# Schematic.net
KiCad netlist of a schematic drawn in Altium Designer
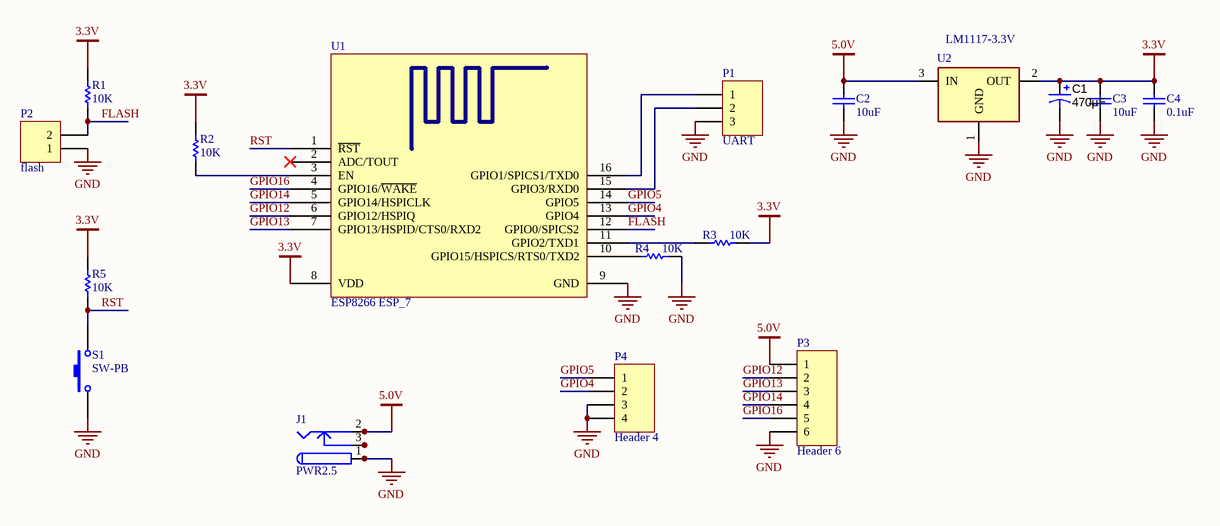
[diagram p0: Schematic.SchDoc]

(export (version "E")
  (design (tool "Eeschema 10.0.6"))
  (components
    (comp (ref "C1")
      (value "T495E477K010ATE040")
      (footprint "7260-38")
      (description "CAP, TANT, 470uF, 10V, +/-10%, 0.04 ohm, 7260-38 SMD")
      (fields
        (field (name "MANUFACTURER") "Kemet")
        (field (name "VALUEDISPLAYED") "470µF")
        (field (name "PUBLISHER") "Texas Instruments")
      )
      (libsource (lib "Schlib1") (part "T495E477K010ATE040"))
    )
    (comp (ref "C2")
      (value "10uF")
      (footprint "C1206")
      (description "Capacitor (Semiconductor SIM Model)")
      (fields (field (name "Comment") "Cap Semi") (field (name "PUBLISHER") "Altium Limited"))
      (libsource (lib "Miscellaneous Devices") (part "Cap Semi"))
    )
    (comp (ref "C3")
      (value "10uF")
      (footprint "C1206")
      (description "Capacitor (Semiconductor SIM Model)")
      (fields (field (name "Comment") "Cap Semi") (field (name "PUBLISHER") "Altium Limited"))
      (libsource (lib "Miscellaneous Devices") (part "Cap Semi"))
    )
    (comp (ref "C4")
      (value "0.1uF")
      (footprint "C1206")
      (description "Capacitor (Semiconductor SIM Model)")
      (fields (field (name "Comment") "Cap Semi") (field (name "PUBLISHER") "Altium Limited"))
      (libsource (lib "Miscellaneous Devices") (part "Cap Semi"))
    )
    (comp (ref "J1")
      (value "PWR2.5")
      (footprint "Jack-DC")
      (description "Low Voltage Power Supply Connector")
      (fields (field (name "PUBLISHER") "Altium Limited"))
      (libsource (lib "Miscellaneous Connectors") (part "PWR2.5"))
    )
    (comp (ref "P1")
      (value "UART")
      (footprint "HDR1X3")
      (description "Header, 3-Pin")
      (fields (field (name "PUBLISHER") "Altium Limited"))
      (libsource (lib "Miscellaneous Connectors") (part "Header 3"))
    )
    (comp (ref "P2")
      (value "flash")
      (footprint "HDR1X2")
      (description "Header, 2-Pin")
      (fields (field (name "PUBLISHER") "Altium Limited"))
      (libsource (lib "Miscellaneous Connectors") (part "Header 2"))
    )
    (comp (ref "P3")
      (value "Header 6")
      (footprint "HDR1X6")
      (description "Header, 6-Pin")
      (fields (field (name "PUBLISHER") "Altium Limited"))
      (libsource (lib "Miscellaneous Connectors") (part "Header 6"))
    )
    (comp (ref "P4")
      (value "Header 4")
      (footprint "HDR1X4")
      (description "Header, 4-Pin")
      (fields (field (name "PUBLISHER") "Altium Limited"))
      (libsource (lib "Miscellaneous Connectors") (part "Header 4"))
    )
    (comp (ref "R1")
      (value "10K")
      (footprint "6-0805_N")
      (description "Resistor")
      (fields (field (name "Comment") "Res1") (field (name "PUBLISHER") "Altium Limited"))
      (libsource (lib "Miscellaneous Devices") (part "Res1"))
    )
    (comp (ref "R2")
      (value "10K")
      (footprint "6-0805_N")
      (description "Resistor")
      (fields (field (name "Comment") "Res1") (field (name "PUBLISHER") "Altium Limited"))
      (libsource (lib "Miscellaneous Devices") (part "Res1"))
    )
    (comp (ref "R3")
      (value "10K")
      (footprint "6-0805_N")
      (description "Resistor")
      (fields (field (name "Comment") "Res1") (field (name "PUBLISHER") "Altium Limited"))
      (libsource (lib "Miscellaneous Devices") (part "Res1"))
    )
    (comp (ref "R4")
      (value "10K")
      (footprint "6-0805_N")
      (description "Resistor")
      (fields (field (name "Comment") "Res1") (field (name "PUBLISHER") "Altium Limited"))
      (libsource (lib "Miscellaneous Devices") (part "Res1"))
    )
    (comp (ref "R5")
      (value "10K")
      (footprint "6-0805_N")
      (description "Resistor")
      (fields (field (name "Comment") "Res1") (field (name "PUBLISHER") "Altium Limited"))
      (libsource (lib "Miscellaneous Devices") (part "Res1"))
    )
    (comp (ref "S1")
      (value "SW-PB")
      (footprint "SW-SMD")
      (description "Switch")
      (fields (field (name "PUBLISHER") "Altium Limited"))
      (libsource (lib "Miscellaneous Devices") (part "SW-PB"))
    )
    (comp (ref "U1")
      (value "ESP8266 ESP_7")
      (footprint "ESP8266:ESP8266 ESP_12")
      (description "ESP8266 ESP-12")
      (fields (field (name "PUBLISHER") "Cynetik Group") (field (name "LATESTREVIEWER") "Zion Blue"))
      (libsource (lib "ESP8266") (part "ESP8266 ESP_12"))
    )
    (comp (ref "U2")
      (value "LM1117-3.3V")
      (footprint "SOT223-4N")
      (description "800mA Low-Dropout Linear Regulator")
      (fields (field (name "CREATOR") "Nguyen Ba Bien"))
      (libsource (lib "Schlib1") (part "LM1117"))
    )
  )
  (nets
    (net (code "1") (name "/FLASH") (class "Default")
      (node (ref "P2") (pin "2") (pinfunction "2_2") (pintype "passive"))
      (node (ref "R1") (pin "1") (pinfunction "1_1") (pintype "passive"))
      (node (ref "U1") (pin "12") (pinfunction "GPIO0/SPICS2_12") (pintype "passive"))
    )
    (net (code "2") (name "/GPIO4") (class "Default")
      (node (ref "P4") (pin "2") (pinfunction "2_2") (pintype "passive"))
      (node (ref "U1") (pin "13") (pinfunction "GPIO4_13") (pintype "passive"))
    )
    (net (code "3") (name "/GPIO5") (class "Default")
      (node (ref "P4") (pin "1") (pinfunction "1_1") (pintype "passive"))
      (node (ref "U1") (pin "14") (pinfunction "GPIO5_14") (pintype "passive"))
    )
    (net (code "4") (name "/GPIO12") (class "Default")
      (node (ref "P3") (pin "2") (pinfunction "2_2") (pintype "passive"))
      (node (ref "U1") (pin "6") (pinfunction "GPIO12/HSPIQ_6") (pintype "passive"))
    )
    (net (code "5") (name "/GPIO13") (class "Default")
      (node (ref "P3") (pin "3") (pinfunction "3_3") (pintype "passive"))
      (node (ref "U1") (pin "7") (pinfunction "GPIO13/HSPID/CTS0/RXD2_7") (pintype "passive"))
    )
    (net (code "6") (name "/GPIO14") (class "Default")
      (node (ref "P3") (pin "4") (pinfunction "4_4") (pintype "passive"))
      (node (ref "U1") (pin "5") (pinfunction "GPIO14/HSPICLK_5") (pintype "passive"))
    )
    (net (code "7") (name "/GPIO16") (class "Default")
      (node (ref "P3") (pin "5") (pinfunction "5_5") (pintype "passive"))
      (node (ref "U1") (pin "4") (pinfunction "GPIO16/~{WAKE}_4") (pintype "passive"))
    )
    (net (code "8") (name "/RST") (class "Default")
      (node (ref "R5") (pin "1") (pinfunction "1_1") (pintype "passive"))
      (node (ref "S1") (pin "2") (pinfunction "2_2") (pintype "passive"))
      (node (ref "U1") (pin "1") (pinfunction "~{RST}_1") (pintype "passive"))
    )
    (net (code "9") (name "3.3V") (class "Default")
      (node (ref "C1") (pin "1") (pinfunction "+_1") (pintype "passive"))
      (node (ref "C3") (pin "2") (pinfunction "2_2") (pintype "passive"))
      (node (ref "C4") (pin "2") (pinfunction "2_2") (pintype "passive"))
      (node (ref "R1") (pin "2") (pinfunction "2_2") (pintype "passive"))
      (node (ref "R2") (pin "2") (pinfunction "2_2") (pintype "passive"))
      (node (ref "R3") (pin "1") (pinfunction "1_1") (pintype "passive"))
      (node (ref "R5") (pin "2") (pinfunction "2_2") (pintype "passive"))
      (node (ref "U1") (pin "8") (pinfunction "VDD_8") (pintype "passive"))
      (node (ref "U2") (pin "2") (pinfunction "OUT_2") (pintype "passive"))
    )
    (net (code "10") (name "5.0V") (class "Default")
      (node (ref "C2") (pin "2") (pinfunction "2_2") (pintype "passive"))
      (node (ref "J1") (pin "2") (pinfunction "2_2") (pintype "power_in"))
      (node (ref "J1") (pin "2A") (pinfunction "2A_2A") (pintype "power_in"))
      (node (ref "J1") (pin "2B") (pinfunction "2B_2B") (pintype "power_in"))
      (node (ref "P3") (pin "1") (pinfunction "1_1") (pintype "passive"))
      (node (ref "U2") (pin "3") (pinfunction "IN_3") (pintype "passive"))
    )
    (net (code "11") (name "GND") (class "Default")
      (node (ref "C1") (pin "2") (pinfunction "-_2") (pintype "passive"))
      (node (ref "C2") (pin "1") (pinfunction "1_1") (pintype "passive"))
      (node (ref "C3") (pin "1") (pinfunction "1_1") (pintype "passive"))
      (node (ref "C4") (pin "1") (pinfunction "1_1") (pintype "passive"))
      (node (ref "J1") (pin "1") (pinfunction "1_1") (pintype "power_in"))
      (node (ref "J1") (pin "1A") (pinfunction "1A_1A") (pintype "power_in"))
      (node (ref "J1") (pin "1B") (pinfunction "1B_1B") (pintype "power_in"))
      (node (ref "P1") (pin "3") (pinfunction "3_3") (pintype "passive"))
      (node (ref "P2") (pin "1") (pinfunction "1_1") (pintype "passive"))
      (node (ref "P3") (pin "6") (pinfunction "6_6") (pintype "passive"))
      (node (ref "P4") (pin "3") (pinfunction "3_3") (pintype "passive"))
      (node (ref "P4") (pin "4") (pinfunction "4_4") (pintype "passive"))
      (node (ref "R4") (pin "1") (pinfunction "1_1") (pintype "passive"))
      (node (ref "S1") (pin "1") (pinfunction "1_1") (pintype "passive"))
      (node (ref "U1") (pin "9") (pinfunction "GND_9") (pintype "passive"))
      (node (ref "U2") (pin "1") (pinfunction "GND_1") (pintype "passive"))
    )
    (net (code "12") (name "Net-(J1-Pad3)") (class "Default")
      (node (ref "J1") (pin "3") (pinfunction "3_3") (pintype "power_in"))
      (node (ref "J1") (pin "3A") (pinfunction "3A_3A") (pintype "power_in"))
      (node (ref "J1") (pin "3B") (pinfunction "3B_3B") (pintype "power_in"))
    )
    (net (code "13") (name "Net-(U1-EN)") (class "Default")
      (node (ref "R2") (pin "1") (pinfunction "1_1") (pintype "passive"))
      (node (ref "U1") (pin "3") (pinfunction "EN_3") (pintype "passive"))
    )
    (net (code "14") (name "Net-(U1-GPIO1{slash}SPICS1{slash}TXD0)") (class "Default")
      (node (ref "P1") (pin "1") (pinfunction "1_1") (pintype "passive"))
      (node (ref "U1") (pin "16") (pinfunction "GPIO1/SPICS1/TXD0_16") (pintype "passive"))
    )
    (net (code "15") (name "Net-(U1-GPIO2{slash}TXD1)") (class "Default")
      (node (ref "R3") (pin "2") (pinfunction "2_2") (pintype "passive"))
      (node (ref "U1") (pin "11") (pinfunction "GPIO2/TXD1_11") (pintype "passive"))
    )
    (net (code "16") (name "Net-(U1-GPIO3{slash}RXD0)") (class "Default")
      (node (ref "P1") (pin "2") (pinfunction "2_2") (pintype "passive"))
      (node (ref "U1") (pin "15") (pinfunction "GPIO3/RXD0_15") (pintype "passive"))
    )
    (net (code "17") (name "Net-(U1-GPIO15{slash}HSPICS{slash}RTS0{slash}TXD2)") (class "Default")
      (node (ref "R4") (pin "2") (pinfunction "2_2") (pintype "passive"))
      (node (ref "U1") (pin "10") (pinfunction "GPIO15/HSPICS/RTS0/TXD2_10") (pintype "passive"))
    )
    (net (code "18") (name "unconnected-(U1-ADC{slash}TOUT-Pad2)") (class "Default")
      (node (ref "U1") (pin "2") (pinfunction "ADC/TOUT_2") (pintype "passive+no_connect"))
    )
  )
)
